# CustomKeyboard.net
KiCad netlist of a schematic drawn in EAGLE
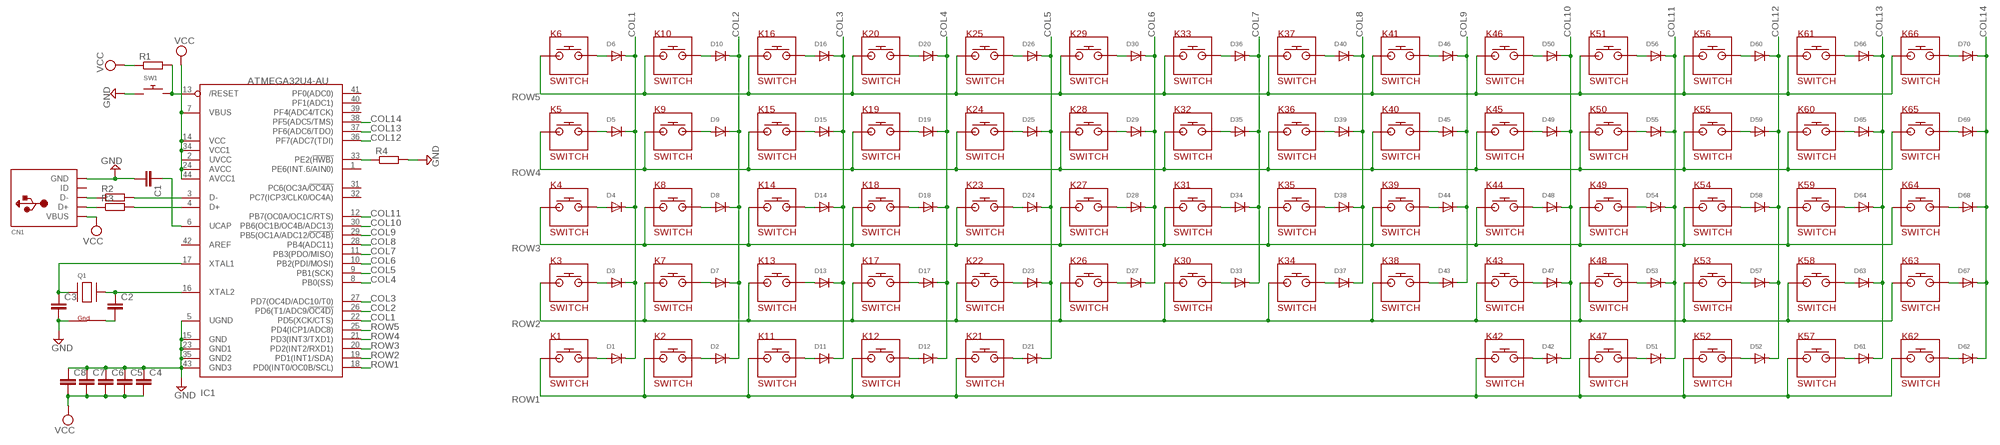
[diagram p0: schematic, sheet 1]

(export (version "E")
  (design (tool "Eeschema 10.0.6"))
  (components
    (comp (ref "C1") (value "C") (footprint "eagle-import:C0805") (libsource (lib "eagle-import") (part "C")))
    (comp (ref "C2") (value "C") (footprint "eagle-import:C0805") (libsource (lib "eagle-import") (part "C")))
    (comp (ref "C3") (value "C") (footprint "eagle-import:C0805") (libsource (lib "eagle-import") (part "C")))
    (comp (ref "C4") (value "C") (footprint "eagle-import:C0805") (libsource (lib "eagle-import") (part "C")))
    (comp (ref "C5") (value "C") (footprint "eagle-import:C0805") (libsource (lib "eagle-import") (part "C")))
    (comp (ref "C6") (value "C") (footprint "eagle-import:C0805") (libsource (lib "eagle-import") (part "C")))
    (comp (ref "C7") (value "C") (footprint "eagle-import:C0805") (libsource (lib "eagle-import") (part "C")))
    (comp (ref "C8") (value "C") (footprint "eagle-import:C0805") (libsource (lib "eagle-import") (part "C")))
    (comp (ref "CN1")
      (value "USBMINIB")
      (footprint "eagle-import:USB-MINIB")
      (libsource (lib "eagle-import") (part "USBMINIB"))
    )
    (comp (ref "D1")
      (value "DIODESMA")
      (footprint "eagle-import:SMADIODE")
      (libsource (lib "eagle-import") (part "DIODESMA"))
    )
    (comp (ref "D2")
      (value "DIODESMA")
      (footprint "eagle-import:SMADIODE")
      (libsource (lib "eagle-import") (part "DIODESMA"))
    )
    (comp (ref "D3")
      (value "DIODESMA")
      (footprint "eagle-import:SMADIODE")
      (libsource (lib "eagle-import") (part "DIODESMA"))
    )
    (comp (ref "D4")
      (value "DIODESMA")
      (footprint "eagle-import:SMADIODE")
      (libsource (lib "eagle-import") (part "DIODESMA"))
    )
    (comp (ref "D5")
      (value "DIODESMA")
      (footprint "eagle-import:SMADIODE")
      (libsource (lib "eagle-import") (part "DIODESMA"))
    )
    (comp (ref "D6")
      (value "DIODESMA")
      (footprint "eagle-import:SMADIODE")
      (libsource (lib "eagle-import") (part "DIODESMA"))
    )
    (comp (ref "D7")
      (value "DIODESMA")
      (footprint "eagle-import:SMADIODE")
      (libsource (lib "eagle-import") (part "DIODESMA"))
    )
    (comp (ref "D8")
      (value "DIODESMA")
      (footprint "eagle-import:SMADIODE")
      (libsource (lib "eagle-import") (part "DIODESMA"))
    )
    (comp (ref "D9")
      (value "DIODESMA")
      (footprint "eagle-import:SMADIODE")
      (libsource (lib "eagle-import") (part "DIODESMA"))
    )
    (comp (ref "D10")
      (value "DIODESMA")
      (footprint "eagle-import:SMADIODE")
      (libsource (lib "eagle-import") (part "DIODESMA"))
    )
    (comp (ref "D11")
      (value "DIODESMA")
      (footprint "eagle-import:SMADIODE")
      (libsource (lib "eagle-import") (part "DIODESMA"))
    )
    (comp (ref "D12")
      (value "DIODESMA")
      (footprint "eagle-import:SMADIODE")
      (libsource (lib "eagle-import") (part "DIODESMA"))
    )
    (comp (ref "D13")
      (value "DIODESMA")
      (footprint "eagle-import:SMADIODE")
      (libsource (lib "eagle-import") (part "DIODESMA"))
    )
    (comp (ref "D14")
      (value "DIODESMA")
      (footprint "eagle-import:SMADIODE")
      (libsource (lib "eagle-import") (part "DIODESMA"))
    )
    (comp (ref "D15")
      (value "DIODESMA")
      (footprint "eagle-import:SMADIODE")
      (libsource (lib "eagle-import") (part "DIODESMA"))
    )
    (comp (ref "D16")
      (value "DIODESMA")
      (footprint "eagle-import:SMADIODE")
      (libsource (lib "eagle-import") (part "DIODESMA"))
    )
    (comp (ref "D17")
      (value "DIODESMA")
      (footprint "eagle-import:SMADIODE")
      (libsource (lib "eagle-import") (part "DIODESMA"))
    )
    (comp (ref "D18")
      (value "DIODESMA")
      (footprint "eagle-import:SMADIODE")
      (libsource (lib "eagle-import") (part "DIODESMA"))
    )
    (comp (ref "D19")
      (value "DIODESMA")
      (footprint "eagle-import:SMADIODE")
      (libsource (lib "eagle-import") (part "DIODESMA"))
    )
    (comp (ref "D20")
      (value "DIODESMA")
      (footprint "eagle-import:SMADIODE")
      (libsource (lib "eagle-import") (part "DIODESMA"))
    )
    (comp (ref "D21")
      (value "DIODESMA")
      (footprint "eagle-import:SMADIODE")
      (libsource (lib "eagle-import") (part "DIODESMA"))
    )
    (comp (ref "D23")
      (value "DIODESMA")
      (footprint "eagle-import:SMADIODE")
      (libsource (lib "eagle-import") (part "DIODESMA"))
    )
    (comp (ref "D24")
      (value "DIODESMA")
      (footprint "eagle-import:SMADIODE")
      (libsource (lib "eagle-import") (part "DIODESMA"))
    )
    (comp (ref "D25")
      (value "DIODESMA")
      (footprint "eagle-import:SMADIODE")
      (libsource (lib "eagle-import") (part "DIODESMA"))
    )
    (comp (ref "D26")
      (value "DIODESMA")
      (footprint "eagle-import:SMADIODE")
      (libsource (lib "eagle-import") (part "DIODESMA"))
    )
    (comp (ref "D27")
      (value "DIODESMA")
      (footprint "eagle-import:SMADIODE")
      (libsource (lib "eagle-import") (part "DIODESMA"))
    )
    (comp (ref "D28")
      (value "DIODESMA")
      (footprint "eagle-import:SMADIODE")
      (libsource (lib "eagle-import") (part "DIODESMA"))
    )
    (comp (ref "D29")
      (value "DIODESMA")
      (footprint "eagle-import:SMADIODE")
      (libsource (lib "eagle-import") (part "DIODESMA"))
    )
    (comp (ref "D30")
      (value "DIODESMA")
      (footprint "eagle-import:SMADIODE")
      (libsource (lib "eagle-import") (part "DIODESMA"))
    )
    (comp (ref "D33")
      (value "DIODESMA")
      (footprint "eagle-import:SMADIODE")
      (libsource (lib "eagle-import") (part "DIODESMA"))
    )
    (comp (ref "D34")
      (value "DIODESMA")
      (footprint "eagle-import:SMADIODE")
      (libsource (lib "eagle-import") (part "DIODESMA"))
    )
    (comp (ref "D35")
      (value "DIODESMA")
      (footprint "eagle-import:SMADIODE")
      (libsource (lib "eagle-import") (part "DIODESMA"))
    )
    (comp (ref "D36")
      (value "DIODESMA")
      (footprint "eagle-import:SMADIODE")
      (libsource (lib "eagle-import") (part "DIODESMA"))
    )
    (comp (ref "D37")
      (value "DIODESMA")
      (footprint "eagle-import:SMADIODE")
      (libsource (lib "eagle-import") (part "DIODESMA"))
    )
    (comp (ref "D38")
      (value "DIODESMA")
      (footprint "eagle-import:SMADIODE")
      (libsource (lib "eagle-import") (part "DIODESMA"))
    )
    (comp (ref "D39")
      (value "DIODESMA")
      (footprint "eagle-import:SMADIODE")
      (libsource (lib "eagle-import") (part "DIODESMA"))
    )
    (comp (ref "D40")
      (value "DIODESMA")
      (footprint "eagle-import:SMADIODE")
      (libsource (lib "eagle-import") (part "DIODESMA"))
    )
    (comp (ref "D42")
      (value "DIODESMA")
      (footprint "eagle-import:SMADIODE")
      (libsource (lib "eagle-import") (part "DIODESMA"))
    )
    (comp (ref "D43")
      (value "DIODESMA")
      (footprint "eagle-import:SMADIODE")
      (libsource (lib "eagle-import") (part "DIODESMA"))
    )
    (comp (ref "D44")
      (value "DIODESMA")
      (footprint "eagle-import:SMADIODE")
      (libsource (lib "eagle-import") (part "DIODESMA"))
    )
    (comp (ref "D45")
      (value "DIODESMA")
      (footprint "eagle-import:SMADIODE")
      (libsource (lib "eagle-import") (part "DIODESMA"))
    )
    (comp (ref "D46")
      (value "DIODESMA")
      (footprint "eagle-import:SMADIODE")
      (libsource (lib "eagle-import") (part "DIODESMA"))
    )
    (comp (ref "D47")
      (value "DIODESMA")
      (footprint "eagle-import:SMADIODE")
      (libsource (lib "eagle-import") (part "DIODESMA"))
    )
    (comp (ref "D48")
      (value "DIODESMA")
      (footprint "eagle-import:SMADIODE")
      (libsource (lib "eagle-import") (part "DIODESMA"))
    )
    (comp (ref "D49")
      (value "DIODESMA")
      (footprint "eagle-import:SMADIODE")
      (libsource (lib "eagle-import") (part "DIODESMA"))
    )
    (comp (ref "D50")
      (value "DIODESMA")
      (footprint "eagle-import:SMADIODE")
      (libsource (lib "eagle-import") (part "DIODESMA"))
    )
    (comp (ref "D51")
      (value "DIODESMA")
      (footprint "eagle-import:SMADIODE")
      (libsource (lib "eagle-import") (part "DIODESMA"))
    )
    (comp (ref "D52")
      (value "DIODESMA")
      (footprint "eagle-import:SMADIODE")
      (libsource (lib "eagle-import") (part "DIODESMA"))
    )
    (comp (ref "D53")
      (value "DIODESMA")
      (footprint "eagle-import:SMADIODE")
      (libsource (lib "eagle-import") (part "DIODESMA"))
    )
    (comp (ref "D54")
      (value "DIODESMA")
      (footprint "eagle-import:SMADIODE")
      (libsource (lib "eagle-import") (part "DIODESMA"))
    )
    (comp (ref "D55")
      (value "DIODESMA")
      (footprint "eagle-import:SMADIODE")
      (libsource (lib "eagle-import") (part "DIODESMA"))
    )
    (comp (ref "D56")
      (value "DIODESMA")
      (footprint "eagle-import:SMADIODE")
      (libsource (lib "eagle-import") (part "DIODESMA"))
    )
    (comp (ref "D57")
      (value "DIODESMA")
      (footprint "eagle-import:SMADIODE")
      (libsource (lib "eagle-import") (part "DIODESMA"))
    )
    (comp (ref "D58")
      (value "DIODESMA")
      (footprint "eagle-import:SMADIODE")
      (libsource (lib "eagle-import") (part "DIODESMA"))
    )
    (comp (ref "D59")
      (value "DIODESMA")
      (footprint "eagle-import:SMADIODE")
      (libsource (lib "eagle-import") (part "DIODESMA"))
    )
    (comp (ref "D60")
      (value "DIODESMA")
      (footprint "eagle-import:SMADIODE")
      (libsource (lib "eagle-import") (part "DIODESMA"))
    )
    (comp (ref "D61")
      (value "DIODESMA")
      (footprint "eagle-import:SMADIODE")
      (libsource (lib "eagle-import") (part "DIODESMA"))
    )
    (comp (ref "D62")
      (value "DIODESMA")
      (footprint "eagle-import:SMADIODE")
      (libsource (lib "eagle-import") (part "DIODESMA"))
    )
    (comp (ref "D63")
      (value "DIODESMA")
      (footprint "eagle-import:SMADIODE")
      (libsource (lib "eagle-import") (part "DIODESMA"))
    )
    (comp (ref "D64")
      (value "DIODESMA")
      (footprint "eagle-import:SMADIODE")
      (libsource (lib "eagle-import") (part "DIODESMA"))
    )
    (comp (ref "D65")
      (value "DIODESMA")
      (footprint "eagle-import:SMADIODE")
      (libsource (lib "eagle-import") (part "DIODESMA"))
    )
    (comp (ref "D66")
      (value "DIODESMA")
      (footprint "eagle-import:SMADIODE")
      (libsource (lib "eagle-import") (part "DIODESMA"))
    )
    (comp (ref "D67")
      (value "DIODESMA")
      (footprint "eagle-import:SMADIODE")
      (libsource (lib "eagle-import") (part "DIODESMA"))
    )
    (comp (ref "D68")
      (value "DIODESMA")
      (footprint "eagle-import:SMADIODE")
      (libsource (lib "eagle-import") (part "DIODESMA"))
    )
    (comp (ref "D69")
      (value "DIODESMA")
      (footprint "eagle-import:SMADIODE")
      (libsource (lib "eagle-import") (part "DIODESMA"))
    )
    (comp (ref "D70")
      (value "DIODESMA")
      (footprint "eagle-import:SMADIODE")
      (libsource (lib "eagle-import") (part "DIODESMA"))
    )
    (comp (ref "IC1")
      (value "ATMEGA32U4-AU")
      (footprint "eagle-import:TQFP44")
      (libsource (lib "eagle-import") (part "ATMEGA32U4-AU"))
    )
    (comp (ref "K1")
      (value "SWITCH")
      (footprint "eagle-import:KAILH_LOW_PROFILE")
      (libsource (lib "eagle-import") (part "SWITCH"))
    )
    (comp (ref "K2")
      (value "SWITCH")
      (footprint "eagle-import:KAILH_LOW_PROFILE")
      (libsource (lib "eagle-import") (part "SWITCH"))
    )
    (comp (ref "K3")
      (value "SWITCH")
      (footprint "eagle-import:KAILH_LOW_PROFILE")
      (libsource (lib "eagle-import") (part "SWITCH"))
    )
    (comp (ref "K4")
      (value "SWITCH")
      (footprint "eagle-import:KAILH_LOW_PROFILE")
      (libsource (lib "eagle-import") (part "SWITCH"))
    )
    (comp (ref "K5")
      (value "SWITCH")
      (footprint "eagle-import:KAILH_LOW_PROFILE")
      (libsource (lib "eagle-import") (part "SWITCH"))
    )
    (comp (ref "K6")
      (value "SWITCH")
      (footprint "eagle-import:KAILH_LOW_PROFILE")
      (libsource (lib "eagle-import") (part "SWITCH"))
    )
    (comp (ref "K7")
      (value "SWITCH")
      (footprint "eagle-import:KAILH_LOW_PROFILE")
      (libsource (lib "eagle-import") (part "SWITCH"))
    )
    (comp (ref "K8")
      (value "SWITCH")
      (footprint "eagle-import:KAILH_LOW_PROFILE")
      (libsource (lib "eagle-import") (part "SWITCH"))
    )
    (comp (ref "K9")
      (value "SWITCH")
      (footprint "eagle-import:KAILH_LOW_PROFILE")
      (libsource (lib "eagle-import") (part "SWITCH"))
    )
    (comp (ref "K10")
      (value "SWITCH")
      (footprint "eagle-import:KAILH_LOW_PROFILE")
      (libsource (lib "eagle-import") (part "SWITCH"))
    )
    (comp (ref "K11")
      (value "SWITCH")
      (footprint "eagle-import:KAILH_LOW_PROFILE")
      (libsource (lib "eagle-import") (part "SWITCH"))
    )
    (comp (ref "K12")
      (value "SWITCH")
      (footprint "eagle-import:KAILH_LOW_PROFILE")
      (libsource (lib "eagle-import") (part "SWITCH"))
    )
    (comp (ref "K13")
      (value "SWITCH")
      (footprint "eagle-import:KAILH_LOW_PROFILE")
      (libsource (lib "eagle-import") (part "SWITCH"))
    )
    (comp (ref "K14")
      (value "SWITCH")
      (footprint "eagle-import:KAILH_LOW_PROFILE")
      (libsource (lib "eagle-import") (part "SWITCH"))
    )
    (comp (ref "K15")
      (value "SWITCH")
      (footprint "eagle-import:KAILH_LOW_PROFILE")
      (libsource (lib "eagle-import") (part "SWITCH"))
    )
    (comp (ref "K16")
      (value "SWITCH")
      (footprint "eagle-import:KAILH_LOW_PROFILE")
      (libsource (lib "eagle-import") (part "SWITCH"))
    )
    (comp (ref "K17")
      (value "SWITCH")
      (footprint "eagle-import:KAILH_LOW_PROFILE")
      (libsource (lib "eagle-import") (part "SWITCH"))
    )
    (comp (ref "K18")
      (value "SWITCH")
      (footprint "eagle-import:KAILH_LOW_PROFILE")
      (libsource (lib "eagle-import") (part "SWITCH"))
    )
    (comp (ref "K19")
      (value "SWITCH")
      (footprint "eagle-import:KAILH_LOW_PROFILE")
      (libsource (lib "eagle-import") (part "SWITCH"))
    )
    (comp (ref "K20")
      (value "SWITCH")
      (footprint "eagle-import:KAILH_LOW_PROFILE")
      (libsource (lib "eagle-import") (part "SWITCH"))
    )
    (comp (ref "K21")
      (value "SWITCH")
      (footprint "eagle-import:KAILH_LOW_PROFILE")
      (libsource (lib "eagle-import") (part "SWITCH"))
    )
    (comp (ref "K22")
      (value "SWITCH")
      (footprint "eagle-import:KAILH_LOW_PROFILE")
      (libsource (lib "eagle-import") (part "SWITCH"))
    )
    (comp (ref "K23")
      (value "SWITCH")
      (footprint "eagle-import:KAILH_LOW_PROFILE")
      (libsource (lib "eagle-import") (part "SWITCH"))
    )
    (comp (ref "K24")
      (value "SWITCH")
      (footprint "eagle-import:KAILH_LOW_PROFILE")
      (libsource (lib "eagle-import") (part "SWITCH"))
    )
    (comp (ref "K25")
      (value "SWITCH")
      (footprint "eagle-import:KAILH_LOW_PROFILE")
      (libsource (lib "eagle-import") (part "SWITCH"))
    )
    (comp (ref "K26")
      (value "SWITCH")
      (footprint "eagle-import:KAILH_LOW_PROFILE")
      (libsource (lib "eagle-import") (part "SWITCH"))
    )
    (comp (ref "K27")
      (value "SWITCH")
      (footprint "eagle-import:KAILH_LOW_PROFILE")
      (libsource (lib "eagle-import") (part "SWITCH"))
    )
    (comp (ref "K28")
      (value "SWITCH")
      (footprint "eagle-import:KAILH_LOW_PROFILE")
      (libsource (lib "eagle-import") (part "SWITCH"))
    )
    (comp (ref "K29")
      (value "SWITCH")
      (footprint "eagle-import:KAILH_LOW_PROFILE")
      (libsource (lib "eagle-import") (part "SWITCH"))
    )
    (comp (ref "K30")
      (value "SWITCH")
      (footprint "eagle-import:KAILH_LOW_PROFILE")
      (libsource (lib "eagle-import") (part "SWITCH"))
    )
    (comp (ref "K31")
      (value "SWITCH")
      (footprint "eagle-import:KAILH_LOW_PROFILE")
      (libsource (lib "eagle-import") (part "SWITCH"))
    )
    (comp (ref "K32")
      (value "SWITCH")
      (footprint "eagle-import:KAILH_LOW_PROFILE")
      (libsource (lib "eagle-import") (part "SWITCH"))
    )
    (comp (ref "K33")
      (value "SWITCH")
      (footprint "eagle-import:KAILH_LOW_PROFILE")
      (libsource (lib "eagle-import") (part "SWITCH"))
    )
    (comp (ref "K34")
      (value "SWITCH")
      (footprint "eagle-import:KAILH_LOW_PROFILE")
      (libsource (lib "eagle-import") (part "SWITCH"))
    )
    (comp (ref "K35")
      (value "SWITCH")
      (footprint "eagle-import:KAILH_LOW_PROFILE")
      (libsource (lib "eagle-import") (part "SWITCH"))
    )
    (comp (ref "K36")
      (value "SWITCH")
      (footprint "eagle-import:KAILH_LOW_PROFILE")
      (libsource (lib "eagle-import") (part "SWITCH"))
    )
    (comp (ref "K37")
      (value "SWITCH")
      (footprint "eagle-import:KAILH_LOW_PROFILE")
      (libsource (lib "eagle-import") (part "SWITCH"))
    )
    (comp (ref "K38")
      (value "SWITCH")
      (footprint "eagle-import:KAILH_LOW_PROFILE")
      (libsource (lib "eagle-import") (part "SWITCH"))
    )
    (comp (ref "K39")
      (value "SWITCH")
      (footprint "eagle-import:KAILH_LOW_PROFILE")
      (libsource (lib "eagle-import") (part "SWITCH"))
    )
    (comp (ref "K40")
      (value "SWITCH")
      (footprint "eagle-import:KAILH_LOW_PROFILE")
      (libsource (lib "eagle-import") (part "SWITCH"))
    )
    (comp (ref "K41")
      (value "SWITCH")
      (footprint "eagle-import:KAILH_LOW_PROFILE")
      (libsource (lib "eagle-import") (part "SWITCH"))
    )
    (comp (ref "K42")
      (value "SWITCH")
      (footprint "eagle-import:KAILH_LOW_PROFILE")
      (libsource (lib "eagle-import") (part "SWITCH"))
    )
    (comp (ref "K43")
      (value "SWITCH")
      (footprint "eagle-import:KAILH_LOW_PROFILE")
      (libsource (lib "eagle-import") (part "SWITCH"))
    )
    (comp (ref "K44")
      (value "SWITCH")
      (footprint "eagle-import:KAILH_LOW_PROFILE")
      (libsource (lib "eagle-import") (part "SWITCH"))
    )
    (comp (ref "K45")
      (value "SWITCH")
      (footprint "eagle-import:KAILH_LOW_PROFILE")
      (libsource (lib "eagle-import") (part "SWITCH"))
    )
    (comp (ref "K46")
      (value "SWITCH")
      (footprint "eagle-import:KAILH_LOW_PROFILE")
      (libsource (lib "eagle-import") (part "SWITCH"))
    )
    (comp (ref "K47")
      (value "SWITCH")
      (footprint "eagle-import:KAILH_LOW_PROFILE")
      (libsource (lib "eagle-import") (part "SWITCH"))
    )
    (comp (ref "K48")
      (value "SWITCH")
      (footprint "eagle-import:KAILH_LOW_PROFILE")
      (libsource (lib "eagle-import") (part "SWITCH"))
    )
    (comp (ref "K49")
      (value "SWITCH")
      (footprint "eagle-import:KAILH_LOW_PROFILE")
      (libsource (lib "eagle-import") (part "SWITCH"))
    )
    (comp (ref "K50")
      (value "SWITCH")
      (footprint "eagle-import:KAILH_LOW_PROFILE")
      (libsource (lib "eagle-import") (part "SWITCH"))
    )
    (comp (ref "K51")
      (value "SWITCH")
      (footprint "eagle-import:KAILH_LOW_PROFILE")
      (libsource (lib "eagle-import") (part "SWITCH"))
    )
    (comp (ref "K52")
      (value "SWITCH")
      (footprint "eagle-import:KAILH_LOW_PROFILE")
      (libsource (lib "eagle-import") (part "SWITCH"))
    )
    (comp (ref "K53")
      (value "SWITCH")
      (footprint "eagle-import:KAILH_LOW_PROFILE")
      (libsource (lib "eagle-import") (part "SWITCH"))
    )
    (comp (ref "K54")
      (value "SWITCH")
      (footprint "eagle-import:KAILH_LOW_PROFILE")
      (libsource (lib "eagle-import") (part "SWITCH"))
    )
    (comp (ref "K55")
      (value "SWITCH")
      (footprint "eagle-import:KAILH_LOW_PROFILE")
      (libsource (lib "eagle-import") (part "SWITCH"))
    )
    (comp (ref "K56")
      (value "SWITCH")
      (footprint "eagle-import:KAILH_LOW_PROFILE")
      (libsource (lib "eagle-import") (part "SWITCH"))
    )
    (comp (ref "K57")
      (value "SWITCH")
      (footprint "eagle-import:KAILH_LOW_PROFILE")
      (libsource (lib "eagle-import") (part "SWITCH"))
    )
    (comp (ref "K58")
      (value "SWITCH")
      (footprint "eagle-import:KAILH_LOW_PROFILE")
      (libsource (lib "eagle-import") (part "SWITCH"))
    )
    (comp (ref "K59")
      (value "SWITCH")
      (footprint "eagle-import:KAILH_LOW_PROFILE")
      (libsource (lib "eagle-import") (part "SWITCH"))
    )
    (comp (ref "K60")
      (value "SWITCH")
      (footprint "eagle-import:KAILH_LOW_PROFILE")
      (libsource (lib "eagle-import") (part "SWITCH"))
    )
    (comp (ref "K61")
      (value "SWITCH")
      (footprint "eagle-import:KAILH_LOW_PROFILE")
      (libsource (lib "eagle-import") (part "SWITCH"))
    )
    (comp (ref "K62")
      (value "SWITCH")
      (footprint "eagle-import:KAILH_LOW_PROFILE")
      (libsource (lib "eagle-import") (part "SWITCH"))
    )
    (comp (ref "K63")
      (value "SWITCH")
      (footprint "eagle-import:KAILH_LOW_PROFILE")
      (libsource (lib "eagle-import") (part "SWITCH"))
    )
    (comp (ref "K64")
      (value "SWITCH")
      (footprint "eagle-import:KAILH_LOW_PROFILE")
      (libsource (lib "eagle-import") (part "SWITCH"))
    )
    (comp (ref "K65")
      (value "SWITCH")
      (footprint "eagle-import:KAILH_LOW_PROFILE")
      (libsource (lib "eagle-import") (part "SWITCH"))
    )
    (comp (ref "K66")
      (value "SWITCH")
      (footprint "eagle-import:KAILH_LOW_PROFILE")
      (libsource (lib "eagle-import") (part "SWITCH"))
    )
    (comp (ref "Q1")
      (value "XTAL-4-3225")
      (footprint "eagle-import:NX3225")
      (libsource (lib "eagle-import") (part "XTAL-4-3225"))
    )
    (comp (ref "R1") (value "R") (footprint "eagle-import:R0805") (libsource (lib "eagle-import") (part "R")))
    (comp (ref "R2") (value "R") (footprint "eagle-import:R0805") (libsource (lib "eagle-import") (part "R")))
    (comp (ref "R3") (value "R") (footprint "eagle-import:R0805") (libsource (lib "eagle-import") (part "R")))
    (comp (ref "R4") (value "R") (footprint "eagle-import:R0805") (libsource (lib "eagle-import") (part "R")))
    (comp (ref "SW1")
      (value "SWITCH_PUSHBUTTONSOFTTOUCHSMD_SJ")
      (footprint "eagle-import:PUSHBUTTON_SMD_SJ")
      (libsource (lib "eagle-import") (part "SWITCH_PUSHBUTTONSOFTTOUCHSMD_SJ"))
    )
  )
  (nets
    (net (code "1") (name "/COL1") (class "Default")
      (node (ref "D1") (pin "C") (pinfunction "C_C") (pintype "passive"))
      (node (ref "D3") (pin "C") (pinfunction "C_C") (pintype "passive"))
      (node (ref "D4") (pin "C") (pinfunction "C_C") (pintype "passive"))
      (node (ref "D5") (pin "C") (pinfunction "C_C") (pintype "passive"))
      (node (ref "D6") (pin "C") (pinfunction "C_C") (pintype "passive"))
      (node (ref "IC1") (pin "22") (pinfunction "PD5(XCK/CTS)_22") (pintype "bidirectional"))
    )
    (net (code "2") (name "/COL2") (class "Default")
      (node (ref "D10") (pin "C") (pinfunction "C_C") (pintype "passive"))
      (node (ref "D2") (pin "C") (pinfunction "C_C") (pintype "passive"))
      (node (ref "D7") (pin "C") (pinfunction "C_C") (pintype "passive"))
      (node (ref "D8") (pin "C") (pinfunction "C_C") (pintype "passive"))
      (node (ref "D9") (pin "C") (pinfunction "C_C") (pintype "passive"))
      (node (ref "IC1") (pin "26") (pinfunction "PD6(T1/ADC9/~{OC4D})_26") (pintype "bidirectional"))
    )
    (net (code "3") (name "/COL3") (class "Default")
      (node (ref "D11") (pin "C") (pinfunction "C_C") (pintype "passive"))
      (node (ref "D13") (pin "C") (pinfunction "C_C") (pintype "passive"))
      (node (ref "D14") (pin "C") (pinfunction "C_C") (pintype "passive"))
      (node (ref "D15") (pin "C") (pinfunction "C_C") (pintype "passive"))
      (node (ref "D16") (pin "C") (pinfunction "C_C") (pintype "passive"))
      (node (ref "IC1") (pin "27") (pinfunction "PD7(OC4D/ADC10/T0)_27") (pintype "bidirectional"))
    )
    (net (code "4") (name "/COL4") (class "Default")
      (node (ref "D12") (pin "C") (pinfunction "C_C") (pintype "passive"))
      (node (ref "D17") (pin "C") (pinfunction "C_C") (pintype "passive"))
      (node (ref "D18") (pin "C") (pinfunction "C_C") (pintype "passive"))
      (node (ref "D19") (pin "C") (pinfunction "C_C") (pintype "passive"))
      (node (ref "D20") (pin "C") (pinfunction "C_C") (pintype "passive"))
      (node (ref "IC1") (pin "8") (pinfunction "PB0(SS)_8") (pintype "bidirectional"))
    )
    (net (code "5") (name "/COL5") (class "Default")
      (node (ref "D21") (pin "C") (pinfunction "C_C") (pintype "passive"))
      (node (ref "D23") (pin "C") (pinfunction "C_C") (pintype "passive"))
      (node (ref "D24") (pin "C") (pinfunction "C_C") (pintype "passive"))
      (node (ref "D25") (pin "C") (pinfunction "C_C") (pintype "passive"))
      (node (ref "D26") (pin "C") (pinfunction "C_C") (pintype "passive"))
      (node (ref "IC1") (pin "9") (pinfunction "PB1(SCK)_9") (pintype "bidirectional"))
    )
    (net (code "6") (name "/COL6") (class "Default")
      (node (ref "D27") (pin "C") (pinfunction "C_C") (pintype "passive"))
      (node (ref "D28") (pin "C") (pinfunction "C_C") (pintype "passive"))
      (node (ref "D29") (pin "C") (pinfunction "C_C") (pintype "passive"))
      (node (ref "D30") (pin "C") (pinfunction "C_C") (pintype "passive"))
      (node (ref "IC1") (pin "10") (pinfunction "PB2(PDI/MOSI)_10") (pintype "bidirectional"))
    )
    (net (code "7") (name "/COL7") (class "Default")
      (node (ref "D33") (pin "C") (pinfunction "C_C") (pintype "passive"))
      (node (ref "D34") (pin "C") (pinfunction "C_C") (pintype "passive"))
      (node (ref "D35") (pin "C") (pinfunction "C_C") (pintype "passive"))
      (node (ref "D36") (pin "C") (pinfunction "C_C") (pintype "passive"))
      (node (ref "IC1") (pin "11") (pinfunction "PB3(PDO/MISO)_11") (pintype "bidirectional"))
    )
    (net (code "8") (name "/COL8") (class "Default")
      (node (ref "D37") (pin "C") (pinfunction "C_C") (pintype "passive"))
      (node (ref "D38") (pin "C") (pinfunction "C_C") (pintype "passive"))
      (node (ref "D39") (pin "C") (pinfunction "C_C") (pintype "passive"))
      (node (ref "D40") (pin "C") (pinfunction "C_C") (pintype "passive"))
      (node (ref "IC1") (pin "28") (pinfunction "PB4(ADC11)_28") (pintype "bidirectional"))
    )
    (net (code "9") (name "/COL9") (class "Default")
      (node (ref "D43") (pin "C") (pinfunction "C_C") (pintype "passive"))
      (node (ref "D44") (pin "C") (pinfunction "C_C") (pintype "passive"))
      (node (ref "D45") (pin "C") (pinfunction "C_C") (pintype "passive"))
      (node (ref "D46") (pin "C") (pinfunction "C_C") (pintype "passive"))
      (node (ref "IC1") (pin "29") (pinfunction "PB5(OC1A/ADC12/~{OC4B})_29") (pintype "bidirectional"))
    )
    (net (code "10") (name "/COL10") (class "Default")
      (node (ref "D42") (pin "C") (pinfunction "C_C") (pintype "passive"))
      (node (ref "D47") (pin "C") (pinfunction "C_C") (pintype "passive"))
      (node (ref "D48") (pin "C") (pinfunction "C_C") (pintype "passive"))
      (node (ref "D49") (pin "C") (pinfunction "C_C") (pintype "passive"))
      (node (ref "D50") (pin "C") (pinfunction "C_C") (pintype "passive"))
      (node (ref "IC1") (pin "30") (pinfunction "PB6(OC1B/OC4B/ADC13)_30") (pintype "bidirectional"))
    )
    (net (code "11") (name "/COL11") (class "Default")
      (node (ref "D51") (pin "C") (pinfunction "C_C") (pintype "passive"))
      (node (ref "D53") (pin "C") (pinfunction "C_C") (pintype "passive"))
      (node (ref "D54") (pin "C") (pinfunction "C_C") (pintype "passive"))
      (node (ref "D55") (pin "C") (pinfunction "C_C") (pintype "passive"))
      (node (ref "D56") (pin "C") (pinfunction "C_C") (pintype "passive"))
      (node (ref "IC1") (pin "12") (pinfunction "PB7(OC0A/OC1C/RTS)_12") (pintype "bidirectional"))
    )
    (net (code "12") (name "/COL12") (class "Default")
      (node (ref "D52") (pin "C") (pinfunction "C_C") (pintype "passive"))
      (node (ref "D57") (pin "C") (pinfunction "C_C") (pintype "passive"))
      (node (ref "D58") (pin "C") (pinfunction "C_C") (pintype "passive"))
      (node (ref "D59") (pin "C") (pinfunction "C_C") (pintype "passive"))
      (node (ref "D60") (pin "C") (pinfunction "C_C") (pintype "passive"))
      (node (ref "IC1") (pin "36") (pinfunction "PF7(ADC7(TDI)_36") (pintype "bidirectional"))
    )
    (net (code "13") (name "/COL13") (class "Default")
      (node (ref "D61") (pin "C") (pinfunction "C_C") (pintype "passive"))
      (node (ref "D63") (pin "C") (pinfunction "C_C") (pintype "passive"))
      (node (ref "D64") (pin "C") (pinfunction "C_C") (pintype "passive"))
      (node (ref "D65") (pin "C") (pinfunction "C_C") (pintype "passive"))
      (node (ref "D66") (pin "C") (pinfunction "C_C") (pintype "passive"))
      (node (ref "IC1") (pin "37") (pinfunction "PF6(ADC6/TDO)_37") (pintype "bidirectional"))
    )
    (net (code "14") (name "/COL14") (class "Default")
      (node (ref "D62") (pin "C") (pinfunction "C_C") (pintype "passive"))
      (node (ref "D67") (pin "C") (pinfunction "C_C") (pintype "passive"))
      (node (ref "D68") (pin "C") (pinfunction "C_C") (pintype "passive"))
      (node (ref "D69") (pin "C") (pinfunction "C_C") (pintype "passive"))
      (node (ref "D70") (pin "C") (pinfunction "C_C") (pintype "passive"))
      (node (ref "IC1") (pin "38") (pinfunction "PF5(ADC5/TMS)_38") (pintype "bidirectional"))
    )
    (net (code "15") (name "/ROW1") (class "Default")
      (node (ref "IC1") (pin "18") (pinfunction "PD0(INT0/OC0B/SCL)_18") (pintype "bidirectional"))
      (node (ref "K1") (pin "P$1") (pinfunction "P$1_P$1") (pintype "bidirectional"))
      (node (ref "K11") (pin "P$1") (pinfunction "P$1_P$1") (pintype "bidirectional"))
      (node (ref "K12") (pin "P$1") (pinfunction "P$1_P$1") (pintype "bidirectional"))
      (node (ref "K2") (pin "P$1") (pinfunction "P$1_P$1") (pintype "bidirectional"))
      (node (ref "K21") (pin "P$1") (pinfunction "P$1_P$1") (pintype "bidirectional"))
      (node (ref "K42") (pin "P$1") (pinfunction "P$1_P$1") (pintype "bidirectional"))
      (node (ref "K47") (pin "P$1") (pinfunction "P$1_P$1") (pintype "bidirectional"))
      (node (ref "K52") (pin "P$1") (pinfunction "P$1_P$1") (pintype "bidirectional"))
      (node (ref "K57") (pin "P$1") (pinfunction "P$1_P$1") (pintype "bidirectional"))
      (node (ref "K62") (pin "P$1") (pinfunction "P$1_P$1") (pintype "bidirectional"))
    )
    (net (code "16") (name "/ROW2") (class "Default")
      (node (ref "IC1") (pin "19") (pinfunction "PD1(INT1/SDA)_19") (pintype "bidirectional"))
      (node (ref "K13") (pin "P$1") (pinfunction "P$1_P$1") (pintype "bidirectional"))
      (node (ref "K17") (pin "P$1") (pinfunction "P$1_P$1") (pintype "bidirectional"))
      (node (ref "K22") (pin "P$1") (pinfunction "P$1_P$1") (pintype "bidirectional"))
      (node (ref "K26") (pin "P$1") (pinfunction "P$1_P$1") (pintype "bidirectional"))
      (node (ref "K3") (pin "P$1") (pinfunction "P$1_P$1") (pintype "bidirectional"))
      (node (ref "K30") (pin "P$1") (pinfunction "P$1_P$1") (pintype "bidirectional"))
      (node (ref "K34") (pin "P$1") (pinfunction "P$1_P$1") (pintype "bidirectional"))
      (node (ref "K38") (pin "P$1") (pinfunction "P$1_P$1") (pintype "bidirectional"))
      (node (ref "K43") (pin "P$1") (pinfunction "P$1_P$1") (pintype "bidirectional"))
      (node (ref "K48") (pin "P$1") (pinfunction "P$1_P$1") (pintype "bidirectional"))
      (node (ref "K53") (pin "P$1") (pinfunction "P$1_P$1") (pintype "bidirectional"))
      (node (ref "K58") (pin "P$1") (pinfunction "P$1_P$1") (pintype "bidirectional"))
      (node (ref "K63") (pin "P$1") (pinfunction "P$1_P$1") (pintype "bidirectional"))
      (node (ref "K7") (pin "P$1") (pinfunction "P$1_P$1") (pintype "bidirectional"))
    )
    (net (code "17") (name "/ROW3") (class "Default")
      (node (ref "IC1") (pin "20") (pinfunction "PD2(INT2/RXD1)_20") (pintype "bidirectional"))
      (node (ref "K14") (pin "P$1") (pinfunction "P$1_P$1") (pintype "bidirectional"))
      (node (ref "K18") (pin "P$1") (pinfunction "P$1_P$1") (pintype "bidirectional"))
      (node (ref "K23") (pin "P$1") (pinfunction "P$1_P$1") (pintype "bidirectional"))
      (node (ref "K27") (pin "P$1") (pinfunction "P$1_P$1") (pintype "bidirectional"))
      (node (ref "K31") (pin "P$1") (pinfunction "P$1_P$1") (pintype "bidirectional"))
      (node (ref "K35") (pin "P$1") (pinfunction "P$1_P$1") (pintype "bidirectional"))
      (node (ref "K39") (pin "P$1") (pinfunction "P$1_P$1") (pintype "bidirectional"))
      (node (ref "K4") (pin "P$1") (pinfunction "P$1_P$1") (pintype "bidirectional"))
      (node (ref "K44") (pin "P$1") (pinfunction "P$1_P$1") (pintype "bidirectional"))
      (node (ref "K49") (pin "P$1") (pinfunction "P$1_P$1") (pintype "bidirectional"))
      (node (ref "K54") (pin "P$1") (pinfunction "P$1_P$1") (pintype "bidirectional"))
      (node (ref "K59") (pin "P$1") (pinfunction "P$1_P$1") (pintype "bidirectional"))
      (node (ref "K64") (pin "P$1") (pinfunction "P$1_P$1") (pintype "bidirectional"))
      (node (ref "K8") (pin "P$1") (pinfunction "P$1_P$1") (pintype "bidirectional"))
    )
    (net (code "18") (name "/ROW4") (class "Default")
      (node (ref "IC1") (pin "21") (pinfunction "PD3(INT3/TXD1)_21") (pintype "bidirectional"))
      (node (ref "K15") (pin "P$1") (pinfunction "P$1_P$1") (pintype "bidirectional"))
      (node (ref "K19") (pin "P$1") (pinfunction "P$1_P$1") (pintype "bidirectional"))
      (node (ref "K24") (pin "P$1") (pinfunction "P$1_P$1") (pintype "bidirectional"))
      (node (ref "K28") (pin "P$1") (pinfunction "P$1_P$1") (pintype "bidirectional"))
      (node (ref "K32") (pin "P$1") (pinfunction "P$1_P$1") (pintype "bidirectional"))
      (node (ref "K36") (pin "P$1") (pinfunction "P$1_P$1") (pintype "bidirectional"))
      (node (ref "K40") (pin "P$1") (pinfunction "P$1_P$1") (pintype "bidirectional"))
      (node (ref "K45") (pin "P$1") (pinfunction "P$1_P$1") (pintype "bidirectional"))
      (node (ref "K5") (pin "P$1") (pinfunction "P$1_P$1") (pintype "bidirectional"))
      (node (ref "K50") (pin "P$1") (pinfunction "P$1_P$1") (pintype "bidirectional"))
      (node (ref "K55") (pin "P$1") (pinfunction "P$1_P$1") (pintype "bidirectional"))
      (node (ref "K60") (pin "P$1") (pinfunction "P$1_P$1") (pintype "bidirectional"))
      (node (ref "K65") (pin "P$1") (pinfunction "P$1_P$1") (pintype "bidirectional"))
      (node (ref "K9") (pin "P$1") (pinfunction "P$1_P$1") (pintype "bidirectional"))
    )
    (net (code "19") (name "/ROW5") (class "Default")
      (node (ref "IC1") (pin "25") (pinfunction "PD4(ICP1/ADC8)_25") (pintype "bidirectional"))
      (node (ref "K10") (pin "P$1") (pinfunction "P$1_P$1") (pintype "bidirectional"))
      (node (ref "K16") (pin "P$1") (pinfunction "P$1_P$1") (pintype "bidirectional"))
      (node (ref "K20") (pin "P$1") (pinfunction "P$1_P$1") (pintype "bidirectional"))
      (node (ref "K25") (pin "P$1") (pinfunction "P$1_P$1") (pintype "bidirectional"))
      (node (ref "K29") (pin "P$1") (pinfunction "P$1_P$1") (pintype "bidirectional"))
      (node (ref "K33") (pin "P$1") (pinfunction "P$1_P$1") (pintype "bidirectional"))
      (node (ref "K37") (pin "P$1") (pinfunction "P$1_P$1") (pintype "bidirectional"))
      (node (ref "K41") (pin "P$1") (pinfunction "P$1_P$1") (pintype "bidirectional"))
      (node (ref "K46") (pin "P$1") (pinfunction "P$1_P$1") (pintype "bidirectional"))
      (node (ref "K51") (pin "P$1") (pinfunction "P$1_P$1") (pintype "bidirectional"))
      (node (ref "K56") (pin "P$1") (pinfunction "P$1_P$1") (pintype "bidirectional"))
      (node (ref "K6") (pin "P$1") (pinfunction "P$1_P$1") (pintype "bidirectional"))
      (node (ref "K61") (pin "P$1") (pinfunction "P$1_P$1") (pintype "bidirectional"))
      (node (ref "K66") (pin "P$1") (pinfunction "P$1_P$1") (pintype "bidirectional"))
    )
    (net (code "20") (name "GND") (class "Default")
      (node (ref "C1") (pin "2") (pinfunction "2_2") (pintype "passive"))
      (node (ref "C3") (pin "2") (pinfunction "2_2") (pintype "passive"))
      (node (ref "C4") (pin "1") (pinfunction "1_1") (pintype "passive"))
      (node (ref "C5") (pin "1") (pinfunction "1_1") (pintype "passive"))
      (node (ref "C6") (pin "1") (pinfunction "1_1") (pintype "passive"))
      (node (ref "C7") (pin "1") (pinfunction "1_1") (pintype "passive"))
      (node (ref "C8") (pin "1") (pinfunction "1_1") (pintype "passive"))
      (node (ref "CN1") (pin "GND") (pinfunction "GND_GND") (pintype "power_in"))
      (node (ref "IC1") (pin "15") (pinfunction "GND_15") (pintype "bidirectional"))
      (node (ref "IC1") (pin "23") (pinfunction "GND1_23") (pintype "bidirectional"))
      (node (ref "IC1") (pin "35") (pinfunction "GND2_35") (pintype "bidirectional"))
      (node (ref "IC1") (pin "43") (pinfunction "GND3_43") (pintype "bidirectional"))
      (node (ref "IC1") (pin "5") (pinfunction "UGND_5") (pintype "bidirectional"))
      (node (ref "Q1") (pin "4") (pinfunction "G1_4") (pintype "power_in"))
      (node (ref "R4") (pin "2") (pinfunction "2_2") (pintype "passive"))
      (node (ref "SW1") (pin "P$1") (pinfunction "P$1_P$1") (pintype "passive"))
    )
    (net (code "21") (name "Net-(CN1-PadD+)") (class "Default")
      (node (ref "CN1") (pin "D+") (pinfunction "D+_D+") (pintype "bidirectional"))
      (node (ref "R3") (pin "1") (pinfunction "1_1") (pintype "passive"))
    )
    (net (code "22") (name "Net-(CN1-PadD-)") (class "Default")
      (node (ref "CN1") (pin "D-") (pinfunction "D-_D-") (pintype "bidirectional"))
      (node (ref "R2") (pin "1") (pinfunction "1_1") (pintype "passive"))
    )
    (net (code "23") (name "Net-(D1-PadA)") (class "Default")
      (node (ref "D1") (pin "A") (pinfunction "A_A") (pintype "passive"))
      (node (ref "K1") (pin "P$2") (pinfunction "P$2_P$2") (pintype "bidirectional"))
    )
    (net (code "24") (name "Net-(D2-PadA)") (class "Default")
      (node (ref "D2") (pin "A") (pinfunction "A_A") (pintype "passive"))
      (node (ref "K2") (pin "P$2") (pinfunction "P$2_P$2") (pintype "bidirectional"))
    )
    (net (code "25") (name "Net-(D3-PadA)") (class "Default")
      (node (ref "D3") (pin "A") (pinfunction "A_A") (pintype "passive"))
      (node (ref "K3") (pin "P$2") (pinfunction "P$2_P$2") (pintype "bidirectional"))
    )
    (net (code "26") (name "Net-(D4-PadA)") (class "Default")
      (node (ref "D4") (pin "A") (pinfunction "A_A") (pintype "passive"))
      (node (ref "K4") (pin "P$2") (pinfunction "P$2_P$2") (pintype "bidirectional"))
    )
    (net (code "27") (name "Net-(D5-PadA)") (class "Default")
      (node (ref "D5") (pin "A") (pinfunction "A_A") (pintype "passive"))
      (node (ref "K5") (pin "P$2") (pinfunction "P$2_P$2") (pintype "bidirectional"))
    )
    (net (code "28") (name "Net-(D6-PadA)") (class "Default")
      (node (ref "D6") (pin "A") (pinfunction "A_A") (pintype "passive"))
      (node (ref "K6") (pin "P$2") (pinfunction "P$2_P$2") (pintype "bidirectional"))
    )
    (net (code "29") (name "Net-(D7-PadA)") (class "Default")
      (node (ref "D7") (pin "A") (pinfunction "A_A") (pintype "passive"))
      (node (ref "K7") (pin "P$2") (pinfunction "P$2_P$2") (pintype "bidirectional"))
    )
    (net (code "30") (name "Net-(D8-PadA)") (class "Default")
      (node (ref "D8") (pin "A") (pinfunction "A_A") (pintype "passive"))
      (node (ref "K8") (pin "P$2") (pinfunction "P$2_P$2") (pintype "bidirectional"))
    )
    (net (code "31") (name "Net-(D9-PadA)") (class "Default")
      (node (ref "D9") (pin "A") (pinfunction "A_A") (pintype "passive"))
      (node (ref "K9") (pin "P$2") (pinfunction "P$2_P$2") (pintype "bidirectional"))
    )
    (net (code "32") (name "Net-(D10-PadA)") (class "Default")
      (node (ref "D10") (pin "A") (pinfunction "A_A") (pintype "passive"))
      (node (ref "K10") (pin "P$2") (pinfunction "P$2_P$2") (pintype "bidirectional"))
    )
    (net (code "33") (name "Net-(D11-PadA)") (class "Default")
      (node (ref "D11") (pin "A") (pinfunction "A_A") (pintype "passive"))
      (node (ref "K11") (pin "P$2") (pinfunction "P$2_P$2") (pintype "bidirectional"))
    )
    (net (code "34") (name "Net-(D12-PadA)") (class "Default")
      (node (ref "D12") (pin "A") (pinfunction "A_A") (pintype "passive"))
      (node (ref "K12") (pin "P$2") (pinfunction "P$2_P$2") (pintype "bidirectional"))
    )
    (net (code "35") (name "Net-(D13-PadA)") (class "Default")
      (node (ref "D13") (pin "A") (pinfunction "A_A") (pintype "passive"))
      (node (ref "K13") (pin "P$2") (pinfunction "P$2_P$2") (pintype "bidirectional"))
    )
    (net (code "36") (name "Net-(D14-PadA)") (class "Default")
      (node (ref "D14") (pin "A") (pinfunction "A_A") (pintype "passive"))
      (node (ref "K14") (pin "P$2") (pinfunction "P$2_P$2") (pintype "bidirectional"))
    )
    (net (code "37") (name "Net-(D15-PadA)") (class "Default")
      (node (ref "D15") (pin "A") (pinfunction "A_A") (pintype "passive"))
      (node (ref "K15") (pin "P$2") (pinfunction "P$2_P$2") (pintype "bidirectional"))
    )
    (net (code "38") (name "Net-(D16-PadA)") (class "Default")
      (node (ref "D16") (pin "A") (pinfunction "A_A") (pintype "passive"))
      (node (ref "K16") (pin "P$2") (pinfunction "P$2_P$2") (pintype "bidirectional"))
    )
    (net (code "39") (name "Net-(D17-PadA)") (class "Default")
      (node (ref "D17") (pin "A") (pinfunction "A_A") (pintype "passive"))
      (node (ref "K17") (pin "P$2") (pinfunction "P$2_P$2") (pintype "bidirectional"))
    )
    (net (code "40") (name "Net-(D18-PadA)") (class "Default")
      (node (ref "D18") (pin "A") (pinfunction "A_A") (pintype "passive"))
      (node (ref "K18") (pin "P$2") (pinfunction "P$2_P$2") (pintype "bidirectional"))
    )
    (net (code "41") (name "Net-(D19-PadA)") (class "Default")
      (node (ref "D19") (pin "A") (pinfunction "A_A") (pintype "passive"))
      (node (ref "K19") (pin "P$2") (pinfunction "P$2_P$2") (pintype "bidirectional"))
    )
    (net (code "42") (name "Net-(D20-PadA)") (class "Default")
      (node (ref "D20") (pin "A") (pinfunction "A_A") (pintype "passive"))
      (node (ref "K20") (pin "P$2") (pinfunction "P$2_P$2") (pintype "bidirectional"))
    )
    (net (code "43") (name "Net-(D21-PadA)") (class "Default")
      (node (ref "D21") (pin "A") (pinfunction "A_A") (pintype "passive"))
      (node (ref "K21") (pin "P$2") (pinfunction "P$2_P$2") (pintype "bidirectional"))
    )
    (net (code "44") (name "Net-(D23-PadA)") (class "Default")
      (node (ref "D23") (pin "A") (pinfunction "A_A") (pintype "passive"))
      (node (ref "K22") (pin "P$2") (pinfunction "P$2_P$2") (pintype "bidirectional"))
    )
    (net (code "45") (name "Net-(D24-PadA)") (class "Default")
      (node (ref "D24") (pin "A") (pinfunction "A_A") (pintype "passive"))
      (node (ref "K23") (pin "P$2") (pinfunction "P$2_P$2") (pintype "bidirectional"))
    )
    (net (code "46") (name "Net-(D25-PadA)") (class "Default")
      (node (ref "D25") (pin "A") (pinfunction "A_A") (pintype "passive"))
      (node (ref "K24") (pin "P$2") (pinfunction "P$2_P$2") (pintype "bidirectional"))
    )
    (net (code "47") (name "Net-(D26-PadA)") (class "Default")
      (node (ref "D26") (pin "A") (pinfunction "A_A") (pintype "passive"))
      (node (ref "K25") (pin "P$2") (pinfunction "P$2_P$2") (pintype "bidirectional"))
    )
    (net (code "48") (name "Net-(D27-PadA)") (class "Default")
      (node (ref "D27") (pin "A") (pinfunction "A_A") (pintype "passive"))
      (node (ref "K26") (pin "P$2") (pinfunction "P$2_P$2") (pintype "bidirectional"))
    )
    (net (code "49") (name "Net-(D28-PadA)") (class "Default")
      (node (ref "D28") (pin "A") (pinfunction "A_A") (pintype "passive"))
      (node (ref "K27") (pin "P$2") (pinfunction "P$2_P$2") (pintype "bidirectional"))
    )
    (net (code "50") (name "Net-(D29-PadA)") (class "Default")
      (node (ref "D29") (pin "A") (pinfunction "A_A") (pintype "passive"))
      (node (ref "K28") (pin "P$2") (pinfunction "P$2_P$2") (pintype "bidirectional"))
    )
    (net (code "51") (name "Net-(D30-PadA)") (class "Default")
      (node (ref "D30") (pin "A") (pinfunction "A_A") (pintype "passive"))
      (node (ref "K29") (pin "P$2") (pinfunction "P$2_P$2") (pintype "bidirectional"))
    )
    (net (code "52") (name "Net-(D33-PadA)") (class "Default")
      (node (ref "D33") (pin "A") (pinfunction "A_A") (pintype "passive"))
      (node (ref "K30") (pin "P$2") (pinfunction "P$2_P$2") (pintype "bidirectional"))
    )
    (net (code "53") (name "Net-(D34-PadA)") (class "Default")
      (node (ref "D34") (pin "A") (pinfunction "A_A") (pintype "passive"))
      (node (ref "K31") (pin "P$2") (pinfunction "P$2_P$2") (pintype "bidirectional"))
    )
    (net (code "54") (name "Net-(D35-PadA)") (class "Default")
      (node (ref "D35") (pin "A") (pinfunction "A_A") (pintype "passive"))
      (node (ref "K32") (pin "P$2") (pinfunction "P$2_P$2") (pintype "bidirectional"))
    )
    (net (code "55") (name "Net-(D36-PadA)") (class "Default")
      (node (ref "D36") (pin "A") (pinfunction "A_A") (pintype "passive"))
      (node (ref "K33") (pin "P$2") (pinfunction "P$2_P$2") (pintype "bidirectional"))
    )
    (net (code "56") (name "Net-(D37-PadA)") (class "Default")
      (node (ref "D37") (pin "A") (pinfunction "A_A") (pintype "passive"))
      (node (ref "K34") (pin "P$2") (pinfunction "P$2_P$2") (pintype "bidirectional"))
    )
    (net (code "57") (name "Net-(D38-PadA)") (class "Default")
      (node (ref "D38") (pin "A") (pinfunction "A_A") (pintype "passive"))
      (node (ref "K35") (pin "P$2") (pinfunction "P$2_P$2") (pintype "bidirectional"))
    )
    (net (code "58") (name "Net-(D39-PadA)") (class "Default")
      (node (ref "D39") (pin "A") (pinfunction "A_A") (pintype "passive"))
      (node (ref "K36") (pin "P$2") (pinfunction "P$2_P$2") (pintype "bidirectional"))
    )
    (net (code "59") (name "Net-(D40-PadA)") (class "Default")
      (node (ref "D40") (pin "A") (pinfunction "A_A") (pintype "passive"))
      (node (ref "K37") (pin "P$2") (pinfunction "P$2_P$2") (pintype "bidirectional"))
    )
    (net (code "60") (name "Net-(D42-PadA)") (class "Default")
      (node (ref "D42") (pin "A") (pinfunction "A_A") (pintype "passive"))
      (node (ref "K42") (pin "P$2") (pinfunction "P$2_P$2") (pintype "bidirectional"))
    )
    (net (code "61") (name "Net-(D43-PadA)") (class "Default")
      (node (ref "D43") (pin "A") (pinfunction "A_A") (pintype "passive"))
      (node (ref "K38") (pin "P$2") (pinfunction "P$2_P$2") (pintype "bidirectional"))
    )
    (net (code "62") (name "Net-(D44-PadA)") (class "Default")
      (node (ref "D44") (pin "A") (pinfunction "A_A") (pintype "passive"))
      (node (ref "K39") (pin "P$2") (pinfunction "P$2_P$2") (pintype "bidirectional"))
    )
    (net (code "63") (name "Net-(D45-PadA)") (class "Default")
      (node (ref "D45") (pin "A") (pinfunction "A_A") (pintype "passive"))
      (node (ref "K40") (pin "P$2") (pinfunction "P$2_P$2") (pintype "bidirectional"))
    )
    (net (code "64") (name "Net-(D46-PadA)") (class "Default")
      (node (ref "D46") (pin "A") (pinfunction "A_A") (pintype "passive"))
      (node (ref "K41") (pin "P$2") (pinfunction "P$2_P$2") (pintype "bidirectional"))
    )
    (net (code "65") (name "Net-(D47-PadA)") (class "Default")
      (node (ref "D47") (pin "A") (pinfunction "A_A") (pintype "passive"))
      (node (ref "K43") (pin "P$2") (pinfunction "P$2_P$2") (pintype "bidirectional"))
    )
    (net (code "66") (name "Net-(D48-PadA)") (class "Default")
      (node (ref "D48") (pin "A") (pinfunction "A_A") (pintype "passive"))
      (node (ref "K44") (pin "P$2") (pinfunction "P$2_P$2") (pintype "bidirectional"))
    )
    (net (code "67") (name "Net-(D49-PadA)") (class "Default")
      (node (ref "D49") (pin "A") (pinfunction "A_A") (pintype "passive"))
      (node (ref "K45") (pin "P$2") (pinfunction "P$2_P$2") (pintype "bidirectional"))
    )
    (net (code "68") (name "Net-(D50-PadA)") (class "Default")
      (node (ref "D50") (pin "A") (pinfunction "A_A") (pintype "passive"))
      (node (ref "K46") (pin "P$2") (pinfunction "P$2_P$2") (pintype "bidirectional"))
    )
    (net (code "69") (name "Net-(D51-PadA)") (class "Default")
      (node (ref "D51") (pin "A") (pinfunction "A_A") (pintype "passive"))
      (node (ref "K47") (pin "P$2") (pinfunction "P$2_P$2") (pintype "bidirectional"))
    )
    (net (code "70") (name "Net-(D52-PadA)") (class "Default")
      (node (ref "D52") (pin "A") (pinfunction "A_A") (pintype "passive"))
      (node (ref "K52") (pin "P$2") (pinfunction "P$2_P$2") (pintype "bidirectional"))
    )
    (net (code "71") (name "Net-(D53-PadA)") (class "Default")
      (node (ref "D53") (pin "A") (pinfunction "A_A") (pintype "passive"))
      (node (ref "K48") (pin "P$2") (pinfunction "P$2_P$2") (pintype "bidirectional"))
    )
    (net (code "72") (name "Net-(D54-PadA)") (class "Default")
      (node (ref "D54") (pin "A") (pinfunction "A_A") (pintype "passive"))
      (node (ref "K49") (pin "P$2") (pinfunction "P$2_P$2") (pintype "bidirectional"))
    )
    (net (code "73") (name "Net-(D55-PadA)") (class "Default")
      (node (ref "D55") (pin "A") (pinfunction "A_A") (pintype "passive"))
      (node (ref "K50") (pin "P$2") (pinfunction "P$2_P$2") (pintype "bidirectional"))
    )
    (net (code "74") (name "Net-(D56-PadA)") (class "Default")
      (node (ref "D56") (pin "A") (pinfunction "A_A") (pintype "passive"))
      (node (ref "K51") (pin "P$2") (pinfunction "P$2_P$2") (pintype "bidirectional"))
    )
    (net (code "75") (name "Net-(D57-PadA)") (class "Default")
      (node (ref "D57") (pin "A") (pinfunction "A_A") (pintype "passive"))
      (node (ref "K53") (pin "P$2") (pinfunction "P$2_P$2") (pintype "bidirectional"))
    )
    (net (code "76") (name "Net-(D58-PadA)") (class "Default")
      (node (ref "D58") (pin "A") (pinfunction "A_A") (pintype "passive"))
      (node (ref "K54") (pin "P$2") (pinfunction "P$2_P$2") (pintype "bidirectional"))
    )
    (net (code "77") (name "Net-(D59-PadA)") (class "Default")
      (node (ref "D59") (pin "A") (pinfunction "A_A") (pintype "passive"))
      (node (ref "K55") (pin "P$2") (pinfunction "P$2_P$2") (pintype "bidirectional"))
    )
    (net (code "78") (name "Net-(D60-PadA)") (class "Default")
      (node (ref "D60") (pin "A") (pinfunction "A_A") (pintype "passive"))
      (node (ref "K56") (pin "P$2") (pinfunction "P$2_P$2") (pintype "bidirectional"))
    )
    (net (code "79") (name "Net-(D61-PadA)") (class "Default")
      (node (ref "D61") (pin "A") (pinfunction "A_A") (pintype "passive"))
      (node (ref "K57") (pin "P$2") (pinfunction "P$2_P$2") (pintype "bidirectional"))
    )
    (net (code "80") (name "Net-(D62-PadA)") (class "Default")
      (node (ref "D62") (pin "A") (pinfunction "A_A") (pintype "passive"))
      (node (ref "K62") (pin "P$2") (pinfunction "P$2_P$2") (pintype "bidirectional"))
    )
    (net (code "81") (name "Net-(D63-PadA)") (class "Default")
      (node (ref "D63") (pin "A") (pinfunction "A_A") (pintype "passive"))
      (node (ref "K58") (pin "P$2") (pinfunction "P$2_P$2") (pintype "bidirectional"))
    )
    (net (code "82") (name "Net-(D64-PadA)") (class "Default")
      (node (ref "D64") (pin "A") (pinfunction "A_A") (pintype "passive"))
      (node (ref "K59") (pin "P$2") (pinfunction "P$2_P$2") (pintype "bidirectional"))
    )
    (net (code "83") (name "Net-(D65-PadA)") (class "Default")
      (node (ref "D65") (pin "A") (pinfunction "A_A") (pintype "passive"))
      (node (ref "K60") (pin "P$2") (pinfunction "P$2_P$2") (pintype "bidirectional"))
    )
    (net (code "84") (name "Net-(D66-PadA)") (class "Default")
      (node (ref "D66") (pin "A") (pinfunction "A_A") (pintype "passive"))
      (node (ref "K61") (pin "P$2") (pinfunction "P$2_P$2") (pintype "bidirectional"))
    )
    (net (code "85") (name "Net-(D67-PadA)") (class "Default")
      (node (ref "D67") (pin "A") (pinfunction "A_A") (pintype "passive"))
      (node (ref "K63") (pin "P$2") (pinfunction "P$2_P$2") (pintype "bidirectional"))
    )
    (net (code "86") (name "Net-(D68-PadA)") (class "Default")
      (node (ref "D68") (pin "A") (pinfunction "A_A") (pintype "passive"))
      (node (ref "K64") (pin "P$2") (pinfunction "P$2_P$2") (pintype "bidirectional"))
    )
    (net (code "87") (name "Net-(D69-PadA)") (class "Default")
      (node (ref "D69") (pin "A") (pinfunction "A_A") (pintype "passive"))
      (node (ref "K65") (pin "P$2") (pinfunction "P$2_P$2") (pintype "bidirectional"))
    )
    (net (code "88") (name "Net-(D70-PadA)") (class "Default")
      (node (ref "D70") (pin "A") (pinfunction "A_A") (pintype "passive"))
      (node (ref "K66") (pin "P$2") (pinfunction "P$2_P$2") (pintype "bidirectional"))
    )
    (net (code "89") (name "Net-(IC1-D+)") (class "Default")
      (node (ref "IC1") (pin "4") (pinfunction "D+_4") (pintype "bidirectional"))
      (node (ref "R3") (pin "2") (pinfunction "2_2") (pintype "passive"))
    )
    (net (code "90") (name "Net-(IC1-D-)") (class "Default")
      (node (ref "IC1") (pin "3") (pinfunction "D-_3") (pintype "bidirectional"))
      (node (ref "R2") (pin "2") (pinfunction "2_2") (pintype "passive"))
    )
    (net (code "91") (name "Net-(IC1-PE2(~{HWB}))") (class "Default")
      (node (ref "IC1") (pin "33") (pinfunction "PE2(~{HWB})_33") (pintype "bidirectional"))
      (node (ref "R4") (pin "1") (pinfunction "1_1") (pintype "passive"))
    )
    (net (code "92") (name "Net-(IC1-UCAP)") (class "Default")
      (node (ref "C1") (pin "1") (pinfunction "1_1") (pintype "passive"))
      (node (ref "IC1") (pin "6") (pinfunction "UCAP_6") (pintype "bidirectional"))
    )
    (net (code "93") (name "Net-(IC1-XTAL1)") (class "Default")
      (node (ref "C3") (pin "1") (pinfunction "1_1") (pintype "passive"))
      (node (ref "IC1") (pin "17") (pinfunction "XTAL1_17") (pintype "bidirectional"))
      (node (ref "Q1") (pin "1") (pinfunction "X1_1") (pintype "bidirectional"))
    )
    (net (code "94") (name "Net-(IC1-XTAL2)") (class "Default")
      (node (ref "C2") (pin "1") (pinfunction "1_1") (pintype "passive"))
      (node (ref "IC1") (pin "16") (pinfunction "XTAL2_16") (pintype "bidirectional"))
      (node (ref "Q1") (pin "3") (pinfunction "X2_3") (pintype "bidirectional"))
    )
    (net (code "95") (name "Net-(IC1-{slash}RESET)") (class "Default")
      (node (ref "IC1") (pin "13") (pinfunction "/RESET_13") (pintype "bidirectional"))
      (node (ref "R1") (pin "2") (pinfunction "2_2") (pintype "passive"))
      (node (ref "SW1") (pin "P$2") (pinfunction "P$2_P$2") (pintype "passive"))
    )
    (net (code "96") (name "Net-(Q1-G2)") (class "Default")
      (node (ref "C2") (pin "2") (pinfunction "2_2") (pintype "passive"))
      (node (ref "Q1") (pin "2") (pinfunction "G2_2") (pintype "power_in"))
    )
    (net (code "97") (name "VCC") (class "Default")
      (node (ref "C4") (pin "2") (pinfunction "2_2") (pintype "passive"))
      (node (ref "C5") (pin "2") (pinfunction "2_2") (pintype "passive"))
      (node (ref "C6") (pin "2") (pinfunction "2_2") (pintype "passive"))
      (node (ref "C7") (pin "2") (pinfunction "2_2") (pintype "passive"))
      (node (ref "C8") (pin "2") (pinfunction "2_2") (pintype "passive"))
      (node (ref "CN1") (pin "VBUS") (pinfunction "VBUS_VBUS") (pintype "power_in"))
      (node (ref "IC1") (pin "14") (pinfunction "VCC_14") (pintype "bidirectional"))
      (node (ref "IC1") (pin "24") (pinfunction "AVCC_24") (pintype "bidirectional"))
      (node (ref "IC1") (pin "34") (pinfunction "VCC1_34") (pintype "bidirectional"))
      (node (ref "IC1") (pin "44") (pinfunction "AVCC1_44") (pintype "bidirectional"))
      (node (ref "IC1") (pin "7") (pinfunction "VBUS_7") (pintype "bidirectional"))
      (node (ref "R1") (pin "1") (pinfunction "1_1") (pintype "passive"))
    )
    (net (code "98") (name "unconnected-(CN1-PadID)") (class "Default")
      (node (ref "CN1") (pin "ID") (pinfunction "ID_ID") (pintype "bidirectional"))
    )
    (net (code "99") (name "unconnected-(IC1-AREF-Pad42)") (class "Default")
      (node (ref "IC1") (pin "42") (pinfunction "AREF_42") (pintype "bidirectional"))
    )
    (net (code "100") (name "unconnected-(IC1-PC6(OC3A{slash}~{OC4A})-Pad31)") (class "Default")
      (node (ref "IC1") (pin "31") (pinfunction "PC6(OC3A/~{OC4A})_31") (pintype "bidirectional"))
    )
    (net (code "101") (name "unconnected-(IC1-PC7(ICP3{slash}CLK0{slash}OC4A)-Pad32)") (class "Default")
      (node (ref "IC1") (pin "32") (pinfunction "PC7(ICP3/CLK0/OC4A)_32") (pintype "bidirectional"))
    )
    (net (code "102") (name "unconnected-(IC1-PE6(INT.6{slash}AIN0)-Pad1)") (class "Default")
      (node (ref "IC1") (pin "1") (pinfunction "PE6(INT.6/AIN0)_1") (pintype "bidirectional"))
    )
    (net (code "103") (name "unconnected-(IC1-PF0(ADC0)-Pad41)") (class "Default")
      (node (ref "IC1") (pin "41") (pinfunction "PF0(ADC0)_41") (pintype "bidirectional"))
    )
    (net (code "104") (name "unconnected-(IC1-PF1(ADC1)-Pad40)") (class "Default")
      (node (ref "IC1") (pin "40") (pinfunction "PF1(ADC1)_40") (pintype "bidirectional"))
    )
    (net (code "105") (name "unconnected-(IC1-PF4(ADC4{slash}TCK)-Pad39)") (class "Default")
      (node (ref "IC1") (pin "39") (pinfunction "PF4(ADC4/TCK)_39") (pintype "bidirectional"))
    )
    (net (code "106") (name "unconnected-(IC1-UVCC-Pad2)") (class "Default")
      (node (ref "IC1") (pin "2") (pinfunction "UVCC_2") (pintype "bidirectional"))
    )
  )
)
